# LCD.net
KiCad netlist of a schematic drawn in Altium Designer
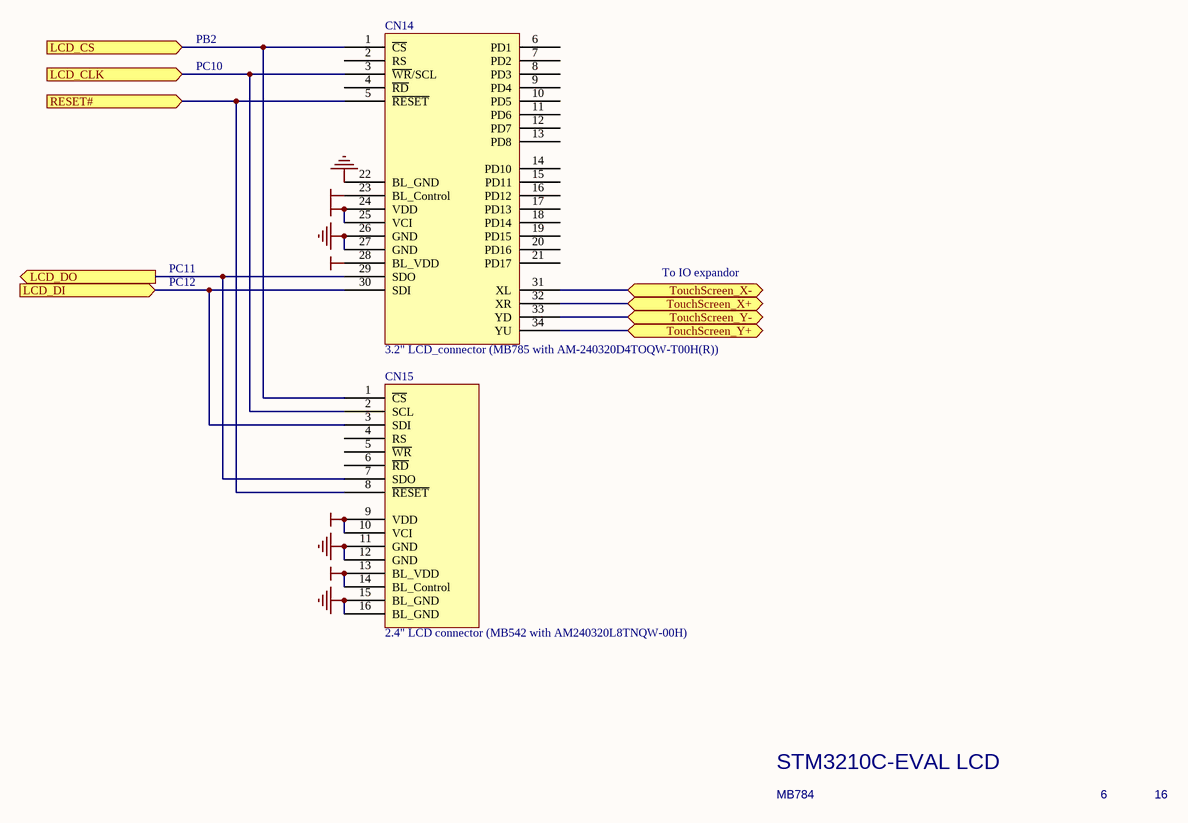
[diagram p0: LCD.SchDoc]

(export (version "E")
  (design (tool "Eeschema 10.0.6"))
  (components
    (comp (ref "CN14")
      (value "3.2\" LCD_connector (MB785 with AM-240320D4TOQW-T00H(R))")
      (footprint "AM240*320AA")
      (libsource (lib "3.2LCD_daughterboard") (part "3.2LCD_connector"))
    )
    (comp (ref "CN15")
      (value "2.4\" LCD connector (MB542 with AM240320L8TNQW-00H)")
      (footprint "AM240*320B")
      (libsource (lib "MB525") (part "ColorLCD_module"))
    )
  )
  (nets
    (net (code "1") (name "+3V3") (class "Default")
      (node (ref "CN14") (pin "24") (pinfunction "VDD_24") (pintype "passive"))
      (node (ref "CN14") (pin "25") (pinfunction "VCI_25") (pintype "passive"))
      (node (ref "CN15") (pin "10") (pinfunction "VCI_10") (pintype "passive"))
      (node (ref "CN15") (pin "13") (pinfunction "BL_VDD_13") (pintype "passive"))
      (node (ref "CN15") (pin "14") (pinfunction "BL_Control_14") (pintype "passive"))
      (node (ref "CN15") (pin "9") (pinfunction "VDD_9") (pintype "passive"))
    )
    (net (code "2") (name "+5V") (class "Default")
      (node (ref "CN14") (pin "23") (pinfunction "BL_Control_23") (pintype "passive"))
      (node (ref "CN14") (pin "28") (pinfunction "BL_VDD_28") (pintype "passive"))
    )
    (net (code "3") (name "/LCD_CLK") (class "Default")
      (node (ref "CN14") (pin "3") (pinfunction "~{WR}/SCL_3") (pintype "passive"))
      (node (ref "CN15") (pin "2") (pinfunction "SCL_2") (pintype "passive"))
    )
    (net (code "4") (name "/LCD_CS") (class "Default")
      (node (ref "CN14") (pin "1") (pinfunction "~{CS}_1") (pintype "passive"))
      (node (ref "CN15") (pin "1") (pinfunction "~{CS}_1") (pintype "passive"))
    )
    (net (code "5") (name "/LCD_DI") (class "Default")
      (node (ref "CN14") (pin "30") (pinfunction "SDI_30") (pintype "passive"))
      (node (ref "CN15") (pin "3") (pinfunction "SDI_3") (pintype "passive"))
    )
    (net (code "6") (name "/LCD_DO") (class "Default")
      (node (ref "CN14") (pin "29") (pinfunction "SDO_29") (pintype "passive"))
      (node (ref "CN15") (pin "7") (pinfunction "SDO_7") (pintype "passive"))
    )
    (net (code "7") (name "/RESET#") (class "Default")
      (node (ref "CN14") (pin "5") (pinfunction "~{RESET}_5") (pintype "passive"))
      (node (ref "CN15") (pin "8") (pinfunction "~{RESET}_8") (pintype "passive"))
    )
    (net (code "8") (name "/TouchScreen_X+") (class "Default")
      (node (ref "CN14") (pin "32") (pinfunction "XR_32") (pintype "passive"))
    )
    (net (code "9") (name "/TouchScreen_X-") (class "Default")
      (node (ref "CN14") (pin "31") (pinfunction "XL_31") (pintype "passive"))
    )
    (net (code "10") (name "/TouchScreen_Y+") (class "Default")
      (node (ref "CN14") (pin "34") (pinfunction "YU_34") (pintype "passive"))
    )
    (net (code "11") (name "/TouchScreen_Y-") (class "Default")
      (node (ref "CN14") (pin "33") (pinfunction "YD_33") (pintype "passive"))
    )
    (net (code "12") (name "GND") (class "Default")
      (node (ref "CN14") (pin "22") (pinfunction "BL_GND_22") (pintype "passive"))
      (node (ref "CN14") (pin "26") (pinfunction "GND_26") (pintype "passive"))
      (node (ref "CN14") (pin "27") (pinfunction "GND_27") (pintype "passive"))
      (node (ref "CN15") (pin "11") (pinfunction "GND_11") (pintype "passive"))
      (node (ref "CN15") (pin "12") (pinfunction "GND_12") (pintype "passive"))
      (node (ref "CN15") (pin "15") (pinfunction "BL_GND_15") (pintype "passive"))
      (node (ref "CN15") (pin "16") (pinfunction "BL_GND_16") (pintype "passive"))
    )
    (net (code "13") (name "unconnected-(CN14-PD1-Pad6)") (class "Default")
      (node (ref "CN14") (pin "6") (pinfunction "PD1_6") (pintype "passive"))
    )
    (net (code "14") (name "unconnected-(CN14-PD2-Pad7)") (class "Default")
      (node (ref "CN14") (pin "7") (pinfunction "PD2_7") (pintype "passive"))
    )
    (net (code "15") (name "unconnected-(CN14-PD3-Pad8)") (class "Default")
      (node (ref "CN14") (pin "8") (pinfunction "PD3_8") (pintype "passive"))
    )
    (net (code "16") (name "unconnected-(CN14-PD4-Pad9)") (class "Default")
      (node (ref "CN14") (pin "9") (pinfunction "PD4_9") (pintype "passive"))
    )
    (net (code "17") (name "unconnected-(CN14-PD5-Pad10)") (class "Default")
      (node (ref "CN14") (pin "10") (pinfunction "PD5_10") (pintype "passive"))
    )
    (net (code "18") (name "unconnected-(CN14-PD6-Pad11)") (class "Default")
      (node (ref "CN14") (pin "11") (pinfunction "PD6_11") (pintype "passive"))
    )
    (net (code "19") (name "unconnected-(CN14-PD7-Pad12)") (class "Default")
      (node (ref "CN14") (pin "12") (pinfunction "PD7_12") (pintype "passive"))
    )
    (net (code "20") (name "unconnected-(CN14-PD8-Pad13)") (class "Default")
      (node (ref "CN14") (pin "13") (pinfunction "PD8_13") (pintype "passive"))
    )
    (net (code "21") (name "unconnected-(CN14-PD10-Pad14)") (class "Default")
      (node (ref "CN14") (pin "14") (pinfunction "PD10_14") (pintype "passive"))
    )
    (net (code "22") (name "unconnected-(CN14-PD11-Pad15)") (class "Default")
      (node (ref "CN14") (pin "15") (pinfunction "PD11_15") (pintype "passive"))
    )
    (net (code "23") (name "unconnected-(CN14-PD12-Pad16)") (class "Default")
      (node (ref "CN14") (pin "16") (pinfunction "PD12_16") (pintype "passive"))
    )
    (net (code "24") (name "unconnected-(CN14-PD13-Pad17)") (class "Default")
      (node (ref "CN14") (pin "17") (pinfunction "PD13_17") (pintype "passive"))
    )
    (net (code "25") (name "unconnected-(CN14-PD14-Pad18)") (class "Default")
      (node (ref "CN14") (pin "18") (pinfunction "PD14_18") (pintype "passive"))
    )
    (net (code "26") (name "unconnected-(CN14-PD15-Pad19)") (class "Default")
      (node (ref "CN14") (pin "19") (pinfunction "PD15_19") (pintype "passive"))
    )
    (net (code "27") (name "unconnected-(CN14-PD16-Pad20)") (class "Default")
      (node (ref "CN14") (pin "20") (pinfunction "PD16_20") (pintype "passive"))
    )
    (net (code "28") (name "unconnected-(CN14-PD17-Pad21)") (class "Default")
      (node (ref "CN14") (pin "21") (pinfunction "PD17_21") (pintype "passive"))
    )
    (net (code "29") (name "unconnected-(CN14-RS-Pad2)") (class "Default")
      (node (ref "CN14") (pin "2") (pinfunction "RS_2") (pintype "passive"))
    )
    (net (code "30") (name "unconnected-(CN14-~{RD}-Pad4)") (class "Default")
      (node (ref "CN14") (pin "4") (pinfunction "~{RD}_4") (pintype "passive"))
    )
    (net (code "31") (name "unconnected-(CN15-RS-Pad4)") (class "Default")
      (node (ref "CN15") (pin "4") (pinfunction "RS_4") (pintype "passive"))
    )
    (net (code "32") (name "unconnected-(CN15-~{RD}-Pad6)") (class "Default")
      (node (ref "CN15") (pin "6") (pinfunction "~{RD}_6") (pintype "passive"))
    )
    (net (code "33") (name "unconnected-(CN15-~{WR}-Pad5)") (class "Default")
      (node (ref "CN15") (pin "5") (pinfunction "~{WR}_5") (pintype "passive"))
    )
  )
)
